# VK49_2_0.net
KiCad netlist of a schematic drawn in EAGLE
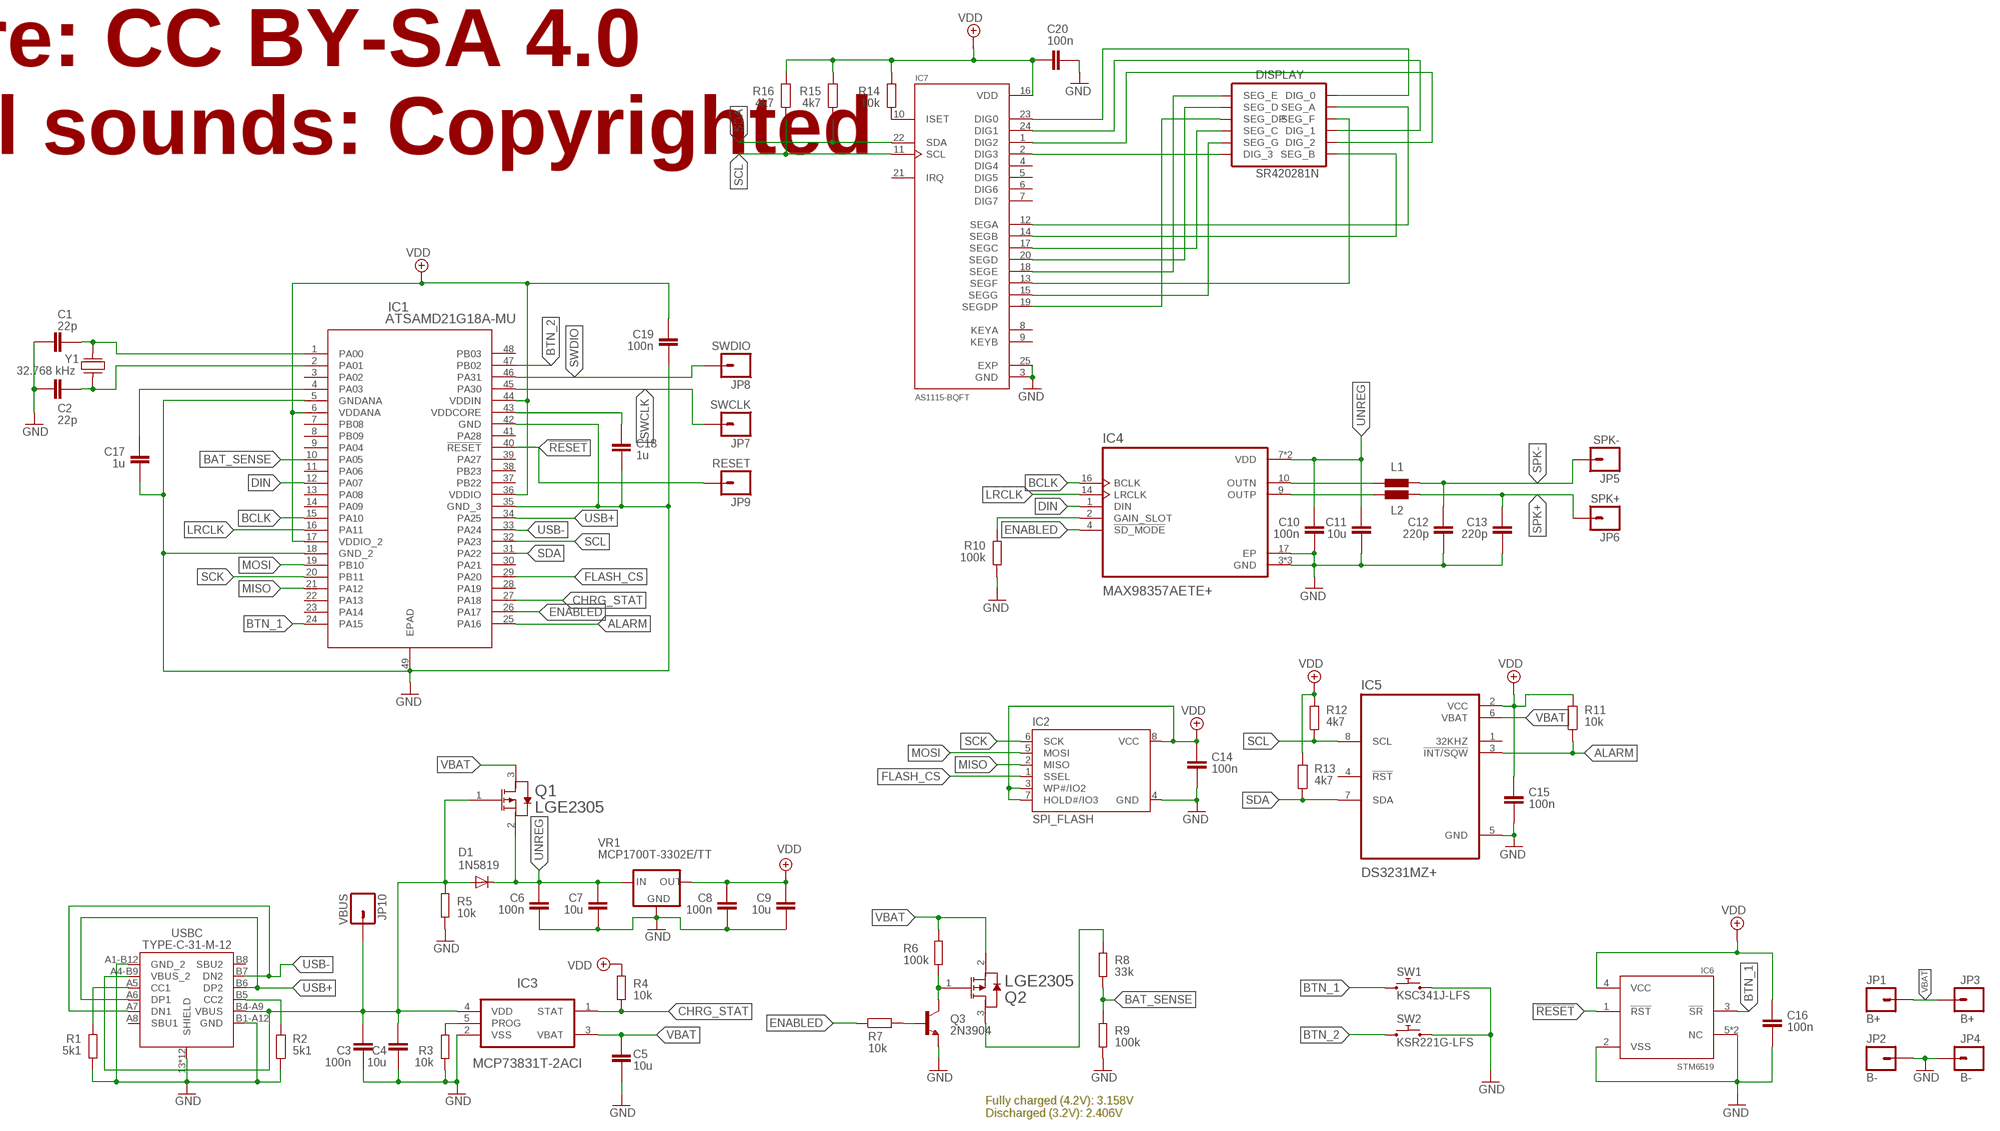
[diagram p0: schematic, sheet 1]

(export (version "E")
  (design (tool "Eeschema 10.0.6"))
  (components
    (comp (ref "C1")
      (value "22p")
      (footprint "eagle-import:CAPACITOR0603")
      (libsource (lib "eagle-import") (part "CAPACITOR0603"))
    )
    (comp (ref "C2")
      (value "22p")
      (footprint "eagle-import:CAPACITOR0603")
      (libsource (lib "eagle-import") (part "CAPACITOR0603"))
    )
    (comp (ref "C3")
      (value "100n")
      (footprint "eagle-import:CAPACITOR0603")
      (libsource (lib "eagle-import") (part "CAPACITOR0603"))
    )
    (comp (ref "C4")
      (value "10u")
      (footprint "eagle-import:CAPACITOR0805")
      (libsource (lib "eagle-import") (part "CAPACITOR0805"))
    )
    (comp (ref "C5")
      (value "10u")
      (footprint "eagle-import:CAPACITOR0805")
      (libsource (lib "eagle-import") (part "CAPACITOR0805"))
    )
    (comp (ref "C6")
      (value "100n")
      (footprint "eagle-import:CAPACITOR0603")
      (libsource (lib "eagle-import") (part "CAPACITOR0603"))
    )
    (comp (ref "C7")
      (value "10u")
      (footprint "eagle-import:CAPACITOR0805")
      (libsource (lib "eagle-import") (part "CAPACITOR0805"))
    )
    (comp (ref "C8")
      (value "100n")
      (footprint "eagle-import:CAPACITOR0603")
      (libsource (lib "eagle-import") (part "CAPACITOR0603"))
    )
    (comp (ref "C9")
      (value "10u")
      (footprint "eagle-import:CAPACITOR0805")
      (libsource (lib "eagle-import") (part "CAPACITOR0805"))
    )
    (comp (ref "C10")
      (value "100n")
      (footprint "eagle-import:CAPACITOR0603")
      (libsource (lib "eagle-import") (part "CAPACITOR0603"))
    )
    (comp (ref "C11")
      (value "10u")
      (footprint "eagle-import:CAPACITOR0805")
      (libsource (lib "eagle-import") (part "CAPACITOR0805"))
    )
    (comp (ref "C12")
      (value "220p")
      (footprint "eagle-import:CAPACITOR0603")
      (libsource (lib "eagle-import") (part "CAPACITOR0603"))
    )
    (comp (ref "C13")
      (value "220p")
      (footprint "eagle-import:CAPACITOR0603")
      (libsource (lib "eagle-import") (part "CAPACITOR0603"))
    )
    (comp (ref "C14")
      (value "100n")
      (footprint "eagle-import:CAPACITOR0603")
      (libsource (lib "eagle-import") (part "CAPACITOR0603"))
    )
    (comp (ref "C15")
      (value "100n")
      (footprint "eagle-import:CAPACITOR0603")
      (libsource (lib "eagle-import") (part "CAPACITOR0603"))
    )
    (comp (ref "C16")
      (value "100n")
      (footprint "eagle-import:CAPACITOR0603")
      (libsource (lib "eagle-import") (part "CAPACITOR0603"))
    )
    (comp (ref "C17")
      (value "1u")
      (footprint "eagle-import:CAPACITOR0603")
      (libsource (lib "eagle-import") (part "CAPACITOR0603"))
    )
    (comp (ref "C18")
      (value "1u")
      (footprint "eagle-import:CAPACITOR0603")
      (libsource (lib "eagle-import") (part "CAPACITOR0603"))
    )
    (comp (ref "C19")
      (value "100n")
      (footprint "eagle-import:CAPACITOR0603")
      (libsource (lib "eagle-import") (part "CAPACITOR0603"))
    )
    (comp (ref "C20")
      (value "100n")
      (footprint "eagle-import:CAPACITOR0603")
      (libsource (lib "eagle-import") (part "CAPACITOR0603"))
    )
    (comp (ref "D1")
      (value "1N5819")
      (footprint "eagle-import:SOD123")
      (fields (field (name "MPN") "CRS01(TE85L,Q,M) "))
      (libsource (lib "eagle-import") (part "CRS01"))
    )
    (comp (ref "DISPLAY")
      (value "SR420281N")
      (footprint "eagle-import:SEG_SR420281N_NO-SILK")
      (libsource (lib "eagle-import") (part "SEG_SR420281N_NOSILK"))
    )
    (comp (ref "IC1")
      (value "ATSAMD21G18A-MU")
      (footprint "eagle-import:QFN-48-7X7")
      (fields
        (field (name "MANUFACTURER_PART_NUMBER") "ATSAMD21G18A-MUT")
        (field (name "COPYRIGHT") "Copyright (C) 2022 Ultra Librarian. All rights reserved.")
      )
      (libsource (lib "eagle-import") (part "ATSAMD21G18A-MU"))
    )
    (comp (ref "IC2")
      (value "SPI_FLASH")
      (footprint "eagle-import:SO08-EIAJ")
      (libsource (lib "eagle-import") (part "SPI_FLASH"))
    )
    (comp (ref "IC3")
      (value "MCP73831T-2ACI")
      (footprint "eagle-import:SOT23-5")
      (fields (field (name "MPN") "MCP73831T-2ACI/OT"))
      (libsource (lib "eagle-import") (part "MCP73831T-2ACI"))
    )
    (comp (ref "IC4")
      (value "MAX98357AETE+")
      (footprint "eagle-import:QFN50P300X300X80-17N")
      (fields (field (name "MF") "Analog Devices"))
      (libsource (lib "eagle-import") (part "MAX98357AETE+"))
    )
    (comp (ref "IC5")
      (value "DS3231MZ+")
      (footprint "eagle-import:SO8")
      (fields
        (field (name "DIGI-KEY_PART_NUMBER") "DS3231MZ+-ND")
        (field (name "MF") "Maxim Integrated Products")
      )
      (libsource (lib "eagle-import") (part "DS3231MZ+"))
    )
    (comp (ref "IC6")
      (value "STM6519")
      (footprint "eagle-import:SON50P145X100X65-6N")
      (fields (field (name "MF") "STMicroelectronics") (field (name "MP") "STM6519AHARUB6F"))
      (libsource (lib "eagle-import") (part "STM6519"))
    )
    (comp (ref "IC7")
      (value "AS1115-BQFT")
      (footprint "eagle-import:QFN50P400X400X65-25N")
      (fields (field (name "DIGI-KEY_PART_NUMBER") "AS1115-BQFTTR-ND") (field (name "MF") "ams"))
      (libsource (lib "eagle-import") (part "AS1115-BQFT"))
    )
    (comp (ref "JP1")
      (value "B+")
      (footprint "eagle-import:1X01_ROUND_NOSILK")
      (libsource (lib "eagle-import") (part "M01_ROUND_NO_SILK"))
    )
    (comp (ref "JP2")
      (value "B-")
      (footprint "eagle-import:1X01_ROUND_NOSILK")
      (libsource (lib "eagle-import") (part "M01_ROUND_NO_SILK"))
    )
    (comp (ref "JP3")
      (value "B+")
      (footprint "eagle-import:1X01_ROUND_NOSILK")
      (libsource (lib "eagle-import") (part "M01_ROUND_NO_SILK"))
    )
    (comp (ref "JP4")
      (value "B-")
      (footprint "eagle-import:1X01_ROUND_NOSILK")
      (libsource (lib "eagle-import") (part "M01_ROUND_NO_SILK"))
    )
    (comp (ref "JP5")
      (value "SPK-")
      (footprint "eagle-import:1X01_ROUND_NOSILK")
      (libsource (lib "eagle-import") (part "M01_ROUND_NO_SILK"))
    )
    (comp (ref "JP6")
      (value "SPK+")
      (footprint "eagle-import:1X01_ROUND_NOSILK")
      (libsource (lib "eagle-import") (part "M01_ROUND_NO_SILK"))
    )
    (comp (ref "JP7")
      (value "SWCLK")
      (footprint "eagle-import:1X01_ROUND_NOSILK")
      (libsource (lib "eagle-import") (part "M01_ROUND_NO_SILK"))
    )
    (comp (ref "JP8")
      (value "SWDIO")
      (footprint "eagle-import:1X01_ROUND_NOSILK")
      (libsource (lib "eagle-import") (part "M01_ROUND_NO_SILK"))
    )
    (comp (ref "JP9")
      (value "RESET")
      (footprint "eagle-import:1X01_ROUND_NOSILK")
      (libsource (lib "eagle-import") (part "M01_ROUND_NO_SILK"))
    )
    (comp (ref "JP10")
      (value "VBUS")
      (footprint "eagle-import:1X01_ROUND_NOSILK")
      (libsource (lib "eagle-import") (part "M01_ROUND_NO_SILK"))
    )
    (comp (ref "L1")
      (value "MMZ1608B121CTAH0")
      (footprint "eagle-import:0603")
      (libsource (lib "eagle-import") (part "BLM15H0603"))
    )
    (comp (ref "L2")
      (value "MMZ1608B121CTAH0")
      (footprint "eagle-import:0603")
      (libsource (lib "eagle-import") (part "BLM15H0603"))
    )
    (comp (ref "Q1")
      (value "LGE2305")
      (footprint "eagle-import:SOT23")
      (libsource (lib "eagle-import") (part "LGE2305"))
    )
    (comp (ref "Q2")
      (value "LGE2305")
      (footprint "eagle-import:SOT23")
      (libsource (lib "eagle-import") (part "LGE2305"))
    )
    (comp (ref "Q3")
      (value "2N3904")
      (footprint "eagle-import:SOT23")
      (fields (field (name "MPN") "MMBT3904LT1G"))
      (libsource (lib "eagle-import") (part "2N3904"))
    )
    (comp (ref "R1")
      (value "5k1")
      (footprint "eagle-import:RESISTOR0603")
      (libsource (lib "eagle-import") (part "RESISTOR0603"))
    )
    (comp (ref "R2")
      (value "5k1")
      (footprint "eagle-import:RESISTOR0603")
      (libsource (lib "eagle-import") (part "RESISTOR0603"))
    )
    (comp (ref "R3")
      (value "10k")
      (footprint "eagle-import:RESISTOR0603")
      (libsource (lib "eagle-import") (part "RESISTOR0603"))
    )
    (comp (ref "R4")
      (value "10k")
      (footprint "eagle-import:RESISTOR0603")
      (libsource (lib "eagle-import") (part "RESISTOR0603"))
    )
    (comp (ref "R5")
      (value "10k")
      (footprint "eagle-import:RESISTOR0603")
      (libsource (lib "eagle-import") (part "RESISTOR0603"))
    )
    (comp (ref "R6")
      (value "100k")
      (footprint "eagle-import:RESISTOR0603")
      (libsource (lib "eagle-import") (part "RESISTOR0603"))
    )
    (comp (ref "R7")
      (value "10k")
      (footprint "eagle-import:RESISTOR0603")
      (libsource (lib "eagle-import") (part "RESISTOR0603"))
    )
    (comp (ref "R8")
      (value "33k")
      (footprint "eagle-import:RESISTOR0603")
      (libsource (lib "eagle-import") (part "RESISTOR0603"))
    )
    (comp (ref "R9")
      (value "100k")
      (footprint "eagle-import:RESISTOR0603")
      (libsource (lib "eagle-import") (part "RESISTOR0603"))
    )
    (comp (ref "R10")
      (value "100k")
      (footprint "eagle-import:RESISTOR0603")
      (libsource (lib "eagle-import") (part "RESISTOR0603"))
    )
    (comp (ref "R11")
      (value "10k")
      (footprint "eagle-import:RESISTOR0603")
      (libsource (lib "eagle-import") (part "RESISTOR0603"))
    )
    (comp (ref "R12")
      (value "4k7")
      (footprint "eagle-import:RESISTOR0603")
      (libsource (lib "eagle-import") (part "RESISTOR0603"))
    )
    (comp (ref "R13")
      (value "4k7")
      (footprint "eagle-import:RESISTOR0603")
      (libsource (lib "eagle-import") (part "RESISTOR0603"))
    )
    (comp (ref "R14")
      (value "10k")
      (footprint "eagle-import:RESISTOR0603")
      (libsource (lib "eagle-import") (part "RESISTOR0603"))
    )
    (comp (ref "R15")
      (value "4k7")
      (footprint "eagle-import:RESISTOR0603")
      (libsource (lib "eagle-import") (part "RESISTOR0603"))
    )
    (comp (ref "R16")
      (value "4k7")
      (footprint "eagle-import:RESISTOR0603")
      (libsource (lib "eagle-import") (part "RESISTOR0603"))
    )
    (comp (ref "SW1")
      (value "KSC341J-LFS")
      (footprint "eagle-import:KSC3XXJ")
      (libsource (lib "eagle-import") (part "KSC3XXJ"))
    )
    (comp (ref "SW2")
      (value "KSR221G-LFS")
      (footprint "eagle-import:KSR2XXG")
      (libsource (lib "eagle-import") (part "KSR2XXG"))
    )
    (comp (ref "USBC")
      (value "TYPE-C-31-M-12")
      (footprint "eagle-import:USB-C")
      (libsource (lib "eagle-import") (part "USB-C"))
    )
    (comp (ref "VR1")
      (value "MCP1700T-3302E/TT")
      (footprint "eagle-import:SOT23")
      (libsource (lib "eagle-import") (part "MCP1700T-3302E/TT"))
    )
    (comp (ref "Y1")
      (value "32.768 kHz")
      (footprint "eagle-import:3.2X1.5-2-PAD")
      (libsource (lib "eagle-import") (part "CRYSTAL_3.2X1.5"))
    )
  )
  (nets
    (net (code "1") (name "/~{RESET}") (class "Default")
      (node (ref "IC1") (pin "40") (pinfunction "~{RESET}_40") (pintype "passive"))
      (node (ref "IC6") (pin "1") (pinfunction "~{RST}_1") (pintype "output"))
      (node (ref "JP9") (pin "1") (pinfunction "1_1") (pintype "passive"))
    )
    (net (code "2") (name "ALARM") (class "Default")
      (node (ref "IC1") (pin "25") (pinfunction "PA16_25") (pintype "bidirectional"))
      (node (ref "IC5") (pin "3") (pinfunction "~{INT/SQW}_3") (pintype "output"))
      (node (ref "R11") (pin "1") (pinfunction "1_1") (pintype "passive"))
    )
    (net (code "3") (name "BAT_SENSE") (class "Default")
      (node (ref "IC1") (pin "10") (pinfunction "PA05_10") (pintype "bidirectional"))
      (node (ref "R8") (pin "2") (pinfunction "2_2") (pintype "passive"))
      (node (ref "R9") (pin "1") (pinfunction "1_1") (pintype "passive"))
    )
    (net (code "4") (name "BCLK") (class "Default")
      (node (ref "IC1") (pin "15") (pinfunction "PA10_15") (pintype "bidirectional"))
      (node (ref "IC4") (pin "16") (pinfunction "BCLK_16") (pintype "input"))
    )
    (net (code "5") (name "BTN_1") (class "Default")
      (node (ref "IC1") (pin "24") (pinfunction "PA15_24") (pintype "bidirectional"))
      (node (ref "IC6") (pin "3") (pinfunction "~{SR}_3") (pintype "input"))
      (node (ref "SW1") (pin "1") (pinfunction "1_1") (pintype "passive"))
      (node (ref "SW1") (pin "3") (pinfunction "1_3") (pintype "passive"))
    )
    (net (code "6") (name "BTN_2") (class "Default")
      (node (ref "IC1") (pin "47") (pinfunction "PB02_47") (pintype "bidirectional"))
      (node (ref "SW2") (pin "1") (pinfunction "1_1") (pintype "passive"))
    )
    (net (code "7") (name "CHRG_STAT") (class "Default")
      (node (ref "IC1") (pin "27") (pinfunction "PA18_27") (pintype "bidirectional"))
      (node (ref "IC3") (pin "1") (pinfunction "STAT_1") (pintype "output"))
      (node (ref "R4") (pin "1") (pinfunction "1_1") (pintype "passive"))
    )
    (net (code "8") (name "DIN") (class "Default")
      (node (ref "IC1") (pin "12") (pinfunction "PA07_12") (pintype "bidirectional"))
      (node (ref "IC4") (pin "1") (pinfunction "DIN_1") (pintype "input"))
    )
    (net (code "9") (name "ENABLED") (class "Default")
      (node (ref "IC1") (pin "26") (pinfunction "PA17_26") (pintype "bidirectional"))
      (node (ref "IC4") (pin "4") (pinfunction "~{SD_MODE}_4") (pintype "input"))
      (node (ref "R7") (pin "1") (pinfunction "1_1") (pintype "passive"))
    )
    (net (code "10") (name "FLASH_CS") (class "Default")
      (node (ref "IC1") (pin "29") (pinfunction "PA20_29") (pintype "bidirectional"))
      (node (ref "IC2") (pin "1") (pinfunction "SSEL_1") (pintype "bidirectional"))
    )
    (net (code "11") (name "GND") (class "Default")
      (node (ref "C1") (pin "1") (pinfunction "1_1") (pintype "passive"))
      (node (ref "C10") (pin "1") (pinfunction "1_1") (pintype "passive"))
      (node (ref "C11") (pin "2") (pinfunction "2_2") (pintype "passive"))
      (node (ref "C12") (pin "1") (pinfunction "1_1") (pintype "passive"))
      (node (ref "C13") (pin "1") (pinfunction "1_1") (pintype "passive"))
      (node (ref "C14") (pin "1") (pinfunction "1_1") (pintype "passive"))
      (node (ref "C15") (pin "1") (pinfunction "1_1") (pintype "passive"))
      (node (ref "C16") (pin "1") (pinfunction "1_1") (pintype "passive"))
      (node (ref "C17") (pin "1") (pinfunction "1_1") (pintype "passive"))
      (node (ref "C18") (pin "1") (pinfunction "1_1") (pintype "passive"))
      (node (ref "C19") (pin "1") (pinfunction "1_1") (pintype "passive"))
      (node (ref "C2") (pin "1") (pinfunction "1_1") (pintype "passive"))
      (node (ref "C20") (pin "1") (pinfunction "1_1") (pintype "passive"))
      (node (ref "C3") (pin "1") (pinfunction "1_1") (pintype "passive"))
      (node (ref "C4") (pin "2") (pinfunction "2_2") (pintype "passive"))
      (node (ref "C5") (pin "2") (pinfunction "2_2") (pintype "passive"))
      (node (ref "C6") (pin "1") (pinfunction "1_1") (pintype "passive"))
      (node (ref "C7") (pin "2") (pinfunction "2_2") (pintype "passive"))
      (node (ref "C8") (pin "1") (pinfunction "1_1") (pintype "passive"))
      (node (ref "C9") (pin "2") (pinfunction "2_2") (pintype "passive"))
      (node (ref "IC1") (pin "18") (pinfunction "GND_2_18") (pintype "passive"))
      (node (ref "IC1") (pin "35") (pinfunction "GND_3_35") (pintype "passive"))
      (node (ref "IC1") (pin "42") (pinfunction "GND_42") (pintype "passive"))
      (node (ref "IC1") (pin "49") (pinfunction "EPAD_49") (pintype "passive"))
      (node (ref "IC1") (pin "5") (pinfunction "GNDANA_5") (pintype "passive"))
      (node (ref "IC2") (pin "4") (pinfunction "GND_4") (pintype "power_in"))
      (node (ref "IC3") (pin "2") (pinfunction "VSS_2") (pintype "power_in"))
      (node (ref "IC4") (pin "11") (pinfunction "GND_11") (pintype "power_in"))
      (node (ref "IC4") (pin "15") (pinfunction "GND_15") (pintype "power_in"))
      (node (ref "IC4") (pin "17") (pinfunction "EP_17") (pintype "power_in"))
      (node (ref "IC4") (pin "3") (pinfunction "GND_3") (pintype "power_in"))
      (node (ref "IC5") (pin "5") (pinfunction "GND_5") (pintype "power_in"))
      (node (ref "IC6") (pin "2") (pinfunction "VSS_2") (pintype "power_in"))
      (node (ref "IC6") (pin "5") (pinfunction "NC_5") (pintype "passive"))
      (node (ref "IC6") (pin "6") (pinfunction "NC_6") (pintype "passive"))
      (node (ref "IC7") (pin "25") (pinfunction "EXP_25") (pintype "passive"))
      (node (ref "IC7") (pin "3") (pinfunction "GND_3") (pintype "power_in"))
      (node (ref "JP2") (pin "1") (pinfunction "1_1") (pintype "passive"))
      (node (ref "JP4") (pin "1") (pinfunction "1_1") (pintype "passive"))
      (node (ref "Q3") (pin "2") (pinfunction "E_2") (pintype "passive"))
      (node (ref "R1") (pin "1") (pinfunction "1_1") (pintype "passive"))
      (node (ref "R10") (pin "1") (pinfunction "1_1") (pintype "passive"))
      (node (ref "R2") (pin "1") (pinfunction "1_1") (pintype "passive"))
      (node (ref "R3") (pin "2") (pinfunction "2_2") (pintype "passive"))
      (node (ref "R5") (pin "1") (pinfunction "1_1") (pintype "passive"))
      (node (ref "R9") (pin "2") (pinfunction "2_2") (pintype "passive"))
      (node (ref "SW1") (pin "2") (pinfunction "2_2") (pintype "passive"))
      (node (ref "SW1") (pin "4") (pinfunction "2_4") (pintype "passive"))
      (node (ref "SW2") (pin "2") (pinfunction "2_2") (pintype "passive"))
      (node (ref "USBC") (pin "13") (pinfunction "SHIELD_13") (pintype "bidirectional"))
      (node (ref "USBC") (pin "14") (pinfunction "SHIELD_14") (pintype "bidirectional"))
      (node (ref "USBC") (pin "15") (pinfunction "SHIELD_15") (pintype "bidirectional"))
      (node (ref "USBC") (pin "16") (pinfunction "SHIELD_16") (pintype "bidirectional"))
      (node (ref "USBC") (pin "A1-B12") (pinfunction "GND_2_A1-B12") (pintype "passive"))
      (node (ref "USBC") (pin "B1-A12") (pinfunction "GND_B1-A12") (pintype "passive"))
      (node (ref "USBC") (pin "S_1_H1") (pinfunction "SHIELD_S_1_H1") (pintype "bidirectional"))
      (node (ref "USBC") (pin "S_1_H2") (pinfunction "SHIELD_S_1_H2") (pintype "bidirectional"))
      (node (ref "USBC") (pin "S_2_H1") (pinfunction "SHIELD_S_2_H1") (pintype "bidirectional"))
      (node (ref "USBC") (pin "S_2_H2") (pinfunction "SHIELD_S_2_H2") (pintype "bidirectional"))
      (node (ref "USBC") (pin "S_3_H1") (pinfunction "SHIELD_S_3_H1") (pintype "bidirectional"))
      (node (ref "USBC") (pin "S_3_H2") (pinfunction "SHIELD_S_3_H2") (pintype "bidirectional"))
      (node (ref "USBC") (pin "S_4_H1") (pinfunction "SHIELD_S_4_H1") (pintype "bidirectional"))
      (node (ref "USBC") (pin "S_4_H2") (pinfunction "SHIELD_S_4_H2") (pintype "bidirectional"))
      (node (ref "VR1") (pin "GND") (pinfunction "GND_GND") (pintype "input"))
    )
    (net (code "12") (name "LRCLK") (class "Default")
      (node (ref "IC1") (pin "16") (pinfunction "PA11_16") (pintype "bidirectional"))
      (node (ref "IC4") (pin "14") (pinfunction "LRCLK_14") (pintype "input"))
    )
    (net (code "13") (name "MISO") (class "Default")
      (node (ref "IC1") (pin "21") (pinfunction "PA12_21") (pintype "bidirectional"))
      (node (ref "IC2") (pin "2") (pinfunction "MISO_2") (pintype "bidirectional"))
    )
    (net (code "14") (name "MOSI") (class "Default")
      (node (ref "IC1") (pin "19") (pinfunction "PB10_19") (pintype "bidirectional"))
      (node (ref "IC2") (pin "5") (pinfunction "MOSI_5") (pintype "bidirectional"))
    )
    (net (code "15") (name "Net-(DISPLAY-DIG_0)") (class "Default")
      (node (ref "DISPLAY") (pin "12") (pinfunction "DIG_0_12") (pintype "bidirectional"))
      (node (ref "IC7") (pin "23") (pinfunction "DIG0_23") (pintype "output"))
    )
    (net (code "16") (name "Net-(DISPLAY-DIG_1)") (class "Default")
      (node (ref "DISPLAY") (pin "9") (pinfunction "DIG_1_9") (pintype "bidirectional"))
      (node (ref "IC7") (pin "24") (pinfunction "DIG1_24") (pintype "output"))
    )
    (net (code "17") (name "Net-(DISPLAY-DIG_2)") (class "Default")
      (node (ref "DISPLAY") (pin "8") (pinfunction "DIG_2_8") (pintype "bidirectional"))
      (node (ref "IC7") (pin "1") (pinfunction "DIG2_1") (pintype "output"))
    )
    (net (code "18") (name "Net-(DISPLAY-DIG_3)") (class "Default")
      (node (ref "DISPLAY") (pin "6") (pinfunction "DIG_3_6") (pintype "bidirectional"))
      (node (ref "IC7") (pin "2") (pinfunction "DIG3_2") (pintype "output"))
    )
    (net (code "19") (name "Net-(DISPLAY-SEG_A)") (class "Default")
      (node (ref "DISPLAY") (pin "11") (pinfunction "SEG_A_11") (pintype "bidirectional"))
      (node (ref "IC7") (pin "12") (pinfunction "SEGA_12") (pintype "output"))
    )
    (net (code "20") (name "Net-(DISPLAY-SEG_B)") (class "Default")
      (node (ref "DISPLAY") (pin "7") (pinfunction "SEG_B_7") (pintype "bidirectional"))
      (node (ref "IC7") (pin "14") (pinfunction "SEGB_14") (pintype "output"))
    )
    (net (code "21") (name "Net-(DISPLAY-SEG_C)") (class "Default")
      (node (ref "DISPLAY") (pin "4") (pinfunction "SEG_C_4") (pintype "bidirectional"))
      (node (ref "IC7") (pin "17") (pinfunction "SEGC_17") (pintype "output"))
    )
    (net (code "22") (name "Net-(DISPLAY-SEG_D)") (class "Default")
      (node (ref "DISPLAY") (pin "2") (pinfunction "SEG_D_2") (pintype "bidirectional"))
      (node (ref "IC7") (pin "20") (pinfunction "SEGD_20") (pintype "output"))
    )
    (net (code "23") (name "Net-(DISPLAY-SEG_DP)") (class "Default")
      (node (ref "DISPLAY") (pin "3") (pinfunction "SEG_DP_3") (pintype "bidirectional"))
      (node (ref "IC7") (pin "19") (pinfunction "SEGDP_19") (pintype "output"))
    )
    (net (code "24") (name "Net-(DISPLAY-SEG_E)") (class "Default")
      (node (ref "DISPLAY") (pin "1") (pinfunction "SEG_E_1") (pintype "bidirectional"))
      (node (ref "IC7") (pin "18") (pinfunction "SEGE_18") (pintype "output"))
    )
    (net (code "25") (name "Net-(DISPLAY-SEG_F)") (class "Default")
      (node (ref "DISPLAY") (pin "10") (pinfunction "SEG_F_10") (pintype "bidirectional"))
      (node (ref "IC7") (pin "13") (pinfunction "SEGF_13") (pintype "output"))
    )
    (net (code "26") (name "Net-(DISPLAY-SEG_G)") (class "Default")
      (node (ref "DISPLAY") (pin "5") (pinfunction "SEG_G_5") (pintype "bidirectional"))
      (node (ref "IC7") (pin "15") (pinfunction "SEGG_15") (pintype "output"))
    )
    (net (code "27") (name "Net-(IC1-PA00)") (class "Default")
      (node (ref "C1") (pin "2") (pinfunction "2_2") (pintype "passive"))
      (node (ref "IC1") (pin "1") (pinfunction "PA00_1") (pintype "bidirectional"))
      (node (ref "Y1") (pin "1") (pinfunction "P$1_1") (pintype "bidirectional"))
    )
    (net (code "28") (name "Net-(IC1-PA01)") (class "Default")
      (node (ref "C2") (pin "2") (pinfunction "2_2") (pintype "passive"))
      (node (ref "IC1") (pin "2") (pinfunction "PA01_2") (pintype "bidirectional"))
      (node (ref "Y1") (pin "2") (pinfunction "P$2_2") (pintype "bidirectional"))
    )
    (net (code "29") (name "Net-(IC1-PA03)") (class "Default")
      (node (ref "C17") (pin "2") (pinfunction "2_2") (pintype "passive"))
      (node (ref "IC1") (pin "4") (pinfunction "PA03_4") (pintype "bidirectional"))
    )
    (net (code "30") (name "Net-(IC1-VDDCORE)") (class "Default")
      (node (ref "C18") (pin "2") (pinfunction "2_2") (pintype "passive"))
      (node (ref "IC1") (pin "43") (pinfunction "VDDCORE_43") (pintype "power_in"))
    )
    (net (code "31") (name "Net-(IC3-PROG)") (class "Default")
      (node (ref "IC3") (pin "5") (pinfunction "PROG_5") (pintype "input"))
      (node (ref "R3") (pin "1") (pinfunction "1_1") (pintype "passive"))
    )
    (net (code "32") (name "Net-(IC3-VDD)") (class "Default")
      (node (ref "C3") (pin "2") (pinfunction "2_2") (pintype "passive"))
      (node (ref "C4") (pin "1") (pinfunction "1_1") (pintype "passive"))
      (node (ref "D1") (pin "A") (pinfunction "A_A") (pintype "passive"))
      (node (ref "IC3") (pin "4") (pinfunction "VDD_4") (pintype "power_in"))
      (node (ref "JP10") (pin "1") (pinfunction "1_1") (pintype "passive"))
      (node (ref "Q1") (pin "1") (pinfunction "GATE_1") (pintype "passive"))
      (node (ref "R5") (pin "2") (pinfunction "2_2") (pintype "passive"))
      (node (ref "USBC") (pin "A4-B9") (pinfunction "VBUS_2_A4-B9") (pintype "power_in"))
      (node (ref "USBC") (pin "B4-A9") (pinfunction "VBUS_B4-A9") (pintype "power_in"))
    )
    (net (code "33") (name "Net-(IC4-GAIN_SLOT)") (class "Default")
      (node (ref "IC4") (pin "2") (pinfunction "GAIN_SLOT_2") (pintype "input"))
      (node (ref "R10") (pin "2") (pinfunction "2_2") (pintype "passive"))
    )
    (net (code "34") (name "Net-(IC4-OUTN)") (class "Default")
      (node (ref "IC4") (pin "10") (pinfunction "OUTN_10") (pintype "output"))
      (node (ref "L1") (pin "1") (pinfunction "1_1") (pintype "passive"))
    )
    (net (code "35") (name "Net-(IC4-OUTP)") (class "Default")
      (node (ref "IC4") (pin "9") (pinfunction "OUTP_9") (pintype "output"))
      (node (ref "L2") (pin "1") (pinfunction "1_1") (pintype "passive"))
    )
    (net (code "36") (name "Net-(IC7-ISET)") (class "Default")
      (node (ref "IC7") (pin "10") (pinfunction "ISET_10") (pintype "passive"))
      (node (ref "R14") (pin "1") (pinfunction "1_1") (pintype "passive"))
    )
    (net (code "37") (name "Net-(Q2-DRAIN)") (class "Default")
      (node (ref "Q2") (pin "3") (pinfunction "DRAIN_3") (pintype "passive"))
      (node (ref "R8") (pin "1") (pinfunction "1_1") (pintype "passive"))
    )
    (net (code "38") (name "Net-(Q2-GATE)") (class "Default")
      (node (ref "Q2") (pin "1") (pinfunction "GATE_1") (pintype "passive"))
      (node (ref "Q3") (pin "3") (pinfunction "C_3") (pintype "passive"))
      (node (ref "R6") (pin "2") (pinfunction "2_2") (pintype "passive"))
    )
    (net (code "39") (name "Net-(Q3-B)") (class "Default")
      (node (ref "Q3") (pin "1") (pinfunction "B_1") (pintype "passive"))
      (node (ref "R7") (pin "2") (pinfunction "2_2") (pintype "passive"))
    )
    (net (code "40") (name "Net-(USBC-CC1)") (class "Default")
      (node (ref "R1") (pin "2") (pinfunction "2_2") (pintype "passive"))
      (node (ref "USBC") (pin "A5") (pinfunction "CC1_A5") (pintype "bidirectional"))
    )
    (net (code "41") (name "Net-(USBC-CC2)") (class "Default")
      (node (ref "R2") (pin "2") (pinfunction "2_2") (pintype "passive"))
      (node (ref "USBC") (pin "B5") (pinfunction "CC2_B5") (pintype "bidirectional"))
    )
    (net (code "42") (name "SCK") (class "Default")
      (node (ref "IC1") (pin "20") (pinfunction "PB11_20") (pintype "bidirectional"))
      (node (ref "IC2") (pin "6") (pinfunction "SCK_6") (pintype "bidirectional"))
    )
    (net (code "43") (name "SCL") (class "Default")
      (node (ref "IC1") (pin "32") (pinfunction "PA23_32") (pintype "bidirectional"))
      (node (ref "IC5") (pin "8") (pinfunction "SCL_8") (pintype "input"))
      (node (ref "IC7") (pin "11") (pinfunction "SCL_11") (pintype "input"))
      (node (ref "R12") (pin "1") (pinfunction "1_1") (pintype "passive"))
      (node (ref "R16") (pin "1") (pinfunction "1_1") (pintype "passive"))
    )
    (net (code "44") (name "SDA") (class "Default")
      (node (ref "IC1") (pin "31") (pinfunction "PA22_31") (pintype "bidirectional"))
      (node (ref "IC5") (pin "7") (pinfunction "SDA_7") (pintype "bidirectional"))
      (node (ref "IC7") (pin "22") (pinfunction "SDA_22") (pintype "bidirectional"))
      (node (ref "R13") (pin "1") (pinfunction "1_1") (pintype "passive"))
      (node (ref "R15") (pin "1") (pinfunction "1_1") (pintype "passive"))
    )
    (net (code "45") (name "SPK+") (class "Default")
      (node (ref "C13") (pin "2") (pinfunction "2_2") (pintype "passive"))
      (node (ref "JP6") (pin "1") (pinfunction "1_1") (pintype "passive"))
      (node (ref "L2") (pin "2") (pinfunction "2_2") (pintype "passive"))
    )
    (net (code "46") (name "SPK-") (class "Default")
      (node (ref "C12") (pin "2") (pinfunction "2_2") (pintype "passive"))
      (node (ref "JP5") (pin "1") (pinfunction "1_1") (pintype "passive"))
      (node (ref "L1") (pin "2") (pinfunction "2_2") (pintype "passive"))
    )
    (net (code "47") (name "SWCLK") (class "Default")
      (node (ref "IC1") (pin "45") (pinfunction "PA30_45") (pintype "bidirectional"))
      (node (ref "JP7") (pin "1") (pinfunction "1_1") (pintype "passive"))
    )
    (net (code "48") (name "SWDIO") (class "Default")
      (node (ref "IC1") (pin "46") (pinfunction "PA31_46") (pintype "bidirectional"))
      (node (ref "JP8") (pin "1") (pinfunction "1_1") (pintype "passive"))
    )
    (net (code "49") (name "UNREG") (class "Default")
      (node (ref "C10") (pin "2") (pinfunction "2_2") (pintype "passive"))
      (node (ref "C11") (pin "1") (pinfunction "1_1") (pintype "passive"))
      (node (ref "C6") (pin "2") (pinfunction "2_2") (pintype "passive"))
      (node (ref "C7") (pin "1") (pinfunction "1_1") (pintype "passive"))
      (node (ref "D1") (pin "C") (pinfunction "C_C") (pintype "passive"))
      (node (ref "IC4") (pin "7") (pinfunction "VDD_7") (pintype "power_in"))
      (node (ref "IC4") (pin "8") (pinfunction "VDD_8") (pintype "power_in"))
      (node (ref "Q1") (pin "2") (pinfunction "SOURCE_2") (pintype "passive"))
      (node (ref "VR1") (pin "VIN") (pinfunction "IN_VIN") (pintype "input"))
    )
    (net (code "50") (name "USB+") (class "Default")
      (node (ref "IC1") (pin "34") (pinfunction "PA25_34") (pintype "bidirectional"))
      (node (ref "USBC") (pin "A6") (pinfunction "DP1_A6") (pintype "bidirectional"))
      (node (ref "USBC") (pin "B6") (pinfunction "DP2_B6") (pintype "bidirectional"))
    )
    (net (code "51") (name "USB-") (class "Default")
      (node (ref "IC1") (pin "33") (pinfunction "PA24_33") (pintype "bidirectional"))
      (node (ref "USBC") (pin "A7") (pinfunction "DN1_A7") (pintype "bidirectional"))
      (node (ref "USBC") (pin "B7") (pinfunction "DN2_B7") (pintype "bidirectional"))
    )
    (net (code "52") (name "VBAT") (class "Default")
      (node (ref "C5") (pin "1") (pinfunction "1_1") (pintype "passive"))
      (node (ref "IC3") (pin "3") (pinfunction "VBAT_3") (pintype "output"))
      (node (ref "IC5") (pin "6") (pinfunction "VBAT_6") (pintype "power_in"))
      (node (ref "JP1") (pin "1") (pinfunction "1_1") (pintype "passive"))
      (node (ref "JP3") (pin "1") (pinfunction "1_1") (pintype "passive"))
      (node (ref "Q1") (pin "3") (pinfunction "DRAIN_3") (pintype "passive"))
      (node (ref "Q2") (pin "2") (pinfunction "SOURCE_2") (pintype "passive"))
      (node (ref "R6") (pin "1") (pinfunction "1_1") (pintype "passive"))
    )
    (net (code "53") (name "VDD") (class "Default")
      (node (ref "C14") (pin "2") (pinfunction "2_2") (pintype "passive"))
      (node (ref "C15") (pin "2") (pinfunction "2_2") (pintype "passive"))
      (node (ref "C16") (pin "2") (pinfunction "2_2") (pintype "passive"))
      (node (ref "C19") (pin "2") (pinfunction "2_2") (pintype "passive"))
      (node (ref "C20") (pin "2") (pinfunction "2_2") (pintype "passive"))
      (node (ref "C8") (pin "2") (pinfunction "2_2") (pintype "passive"))
      (node (ref "C9") (pin "1") (pinfunction "1_1") (pintype "passive"))
      (node (ref "IC1") (pin "17") (pinfunction "VDDIO_2_17") (pintype "power_in"))
      (node (ref "IC1") (pin "36") (pinfunction "VDDIO_36") (pintype "power_in"))
      (node (ref "IC1") (pin "44") (pinfunction "VDDIN_44") (pintype "power_in"))
      (node (ref "IC1") (pin "6") (pinfunction "VDDANA_6") (pintype "power_in"))
      (node (ref "IC2") (pin "3") (pinfunction "WP#/IO2_3") (pintype "bidirectional"))
      (node (ref "IC2") (pin "7") (pinfunction "HOLD#/IO3_7") (pintype "bidirectional"))
      (node (ref "IC2") (pin "8") (pinfunction "VCC_8") (pintype "power_in"))
      (node (ref "IC5") (pin "2") (pinfunction "VCC_2") (pintype "power_in"))
      (node (ref "IC6") (pin "4") (pinfunction "VCC_4") (pintype "power_in"))
      (node (ref "IC7") (pin "16") (pinfunction "VDD_16") (pintype "power_in"))
      (node (ref "R11") (pin "2") (pinfunction "2_2") (pintype "passive"))
      (node (ref "R12") (pin "2") (pinfunction "2_2") (pintype "passive"))
      (node (ref "R13") (pin "2") (pinfunction "2_2") (pintype "passive"))
      (node (ref "R14") (pin "2") (pinfunction "2_2") (pintype "passive"))
      (node (ref "R15") (pin "2") (pinfunction "2_2") (pintype "passive"))
      (node (ref "R16") (pin "2") (pinfunction "2_2") (pintype "passive"))
      (node (ref "R4") (pin "2") (pinfunction "2_2") (pintype "passive"))
      (node (ref "VR1") (pin "VOUT") (pinfunction "OUT_VOUT") (pintype "output"))
    )
    (net (code "54") (name "unconnected-(IC1-PA02-Pad3)") (class "Default")
      (node (ref "IC1") (pin "3") (pinfunction "PA02_3") (pintype "bidirectional"))
    )
    (net (code "55") (name "unconnected-(IC1-PA04-Pad9)") (class "Default")
      (node (ref "IC1") (pin "9") (pinfunction "PA04_9") (pintype "bidirectional"))
    )
    (net (code "56") (name "unconnected-(IC1-PA06-Pad11)") (class "Default")
      (node (ref "IC1") (pin "11") (pinfunction "PA06_11") (pintype "bidirectional"))
    )
    (net (code "57") (name "unconnected-(IC1-PA08-Pad13)") (class "Default")
      (node (ref "IC1") (pin "13") (pinfunction "PA08_13") (pintype "bidirectional"))
    )
    (net (code "58") (name "unconnected-(IC1-PA09-Pad14)") (class "Default")
      (node (ref "IC1") (pin "14") (pinfunction "PA09_14") (pintype "bidirectional"))
    )
    (net (code "59") (name "unconnected-(IC1-PA13-Pad22)") (class "Default")
      (node (ref "IC1") (pin "22") (pinfunction "PA13_22") (pintype "bidirectional"))
    )
    (net (code "60") (name "unconnected-(IC1-PA14-Pad23)") (class "Default")
      (node (ref "IC1") (pin "23") (pinfunction "PA14_23") (pintype "bidirectional"))
    )
    (net (code "61") (name "unconnected-(IC1-PA19-Pad28)") (class "Default")
      (node (ref "IC1") (pin "28") (pinfunction "PA19_28") (pintype "bidirectional"))
    )
    (net (code "62") (name "unconnected-(IC1-PA21-Pad30)") (class "Default")
      (node (ref "IC1") (pin "30") (pinfunction "PA21_30") (pintype "bidirectional"))
    )
    (net (code "63") (name "unconnected-(IC1-PA27-Pad39)") (class "Default")
      (node (ref "IC1") (pin "39") (pinfunction "PA27_39") (pintype "bidirectional"))
    )
    (net (code "64") (name "unconnected-(IC1-PA28-Pad41)") (class "Default")
      (node (ref "IC1") (pin "41") (pinfunction "PA28_41") (pintype "bidirectional"))
    )
    (net (code "65") (name "unconnected-(IC1-PB03-Pad48)") (class "Default")
      (node (ref "IC1") (pin "48") (pinfunction "PB03_48") (pintype "bidirectional"))
    )
    (net (code "66") (name "unconnected-(IC1-PB08-Pad7)") (class "Default")
      (node (ref "IC1") (pin "7") (pinfunction "PB08_7") (pintype "bidirectional"))
    )
    (net (code "67") (name "unconnected-(IC1-PB09-Pad8)") (class "Default")
      (node (ref "IC1") (pin "8") (pinfunction "PB09_8") (pintype "bidirectional"))
    )
    (net (code "68") (name "unconnected-(IC1-PB22-Pad37)") (class "Default")
      (node (ref "IC1") (pin "37") (pinfunction "PB22_37") (pintype "bidirectional"))
    )
    (net (code "69") (name "unconnected-(IC1-PB23-Pad38)") (class "Default")
      (node (ref "IC1") (pin "38") (pinfunction "PB23_38") (pintype "bidirectional"))
    )
    (net (code "70") (name "unconnected-(IC5-32KHZ-Pad1)") (class "Default")
      (node (ref "IC5") (pin "1") (pinfunction "32KHZ_1") (pintype "output"))
    )
    (net (code "71") (name "unconnected-(IC5-~{RST}-Pad4)") (class "Default")
      (node (ref "IC5") (pin "4") (pinfunction "~{RST}_4") (pintype "bidirectional"))
    )
    (net (code "72") (name "unconnected-(IC7-DIG4-Pad4)") (class "Default")
      (node (ref "IC7") (pin "4") (pinfunction "DIG4_4") (pintype "output"))
    )
    (net (code "73") (name "unconnected-(IC7-DIG5-Pad5)") (class "Default")
      (node (ref "IC7") (pin "5") (pinfunction "DIG5_5") (pintype "output"))
    )
    (net (code "74") (name "unconnected-(IC7-DIG6-Pad6)") (class "Default")
      (node (ref "IC7") (pin "6") (pinfunction "DIG6_6") (pintype "output"))
    )
    (net (code "75") (name "unconnected-(IC7-DIG7-Pad7)") (class "Default")
      (node (ref "IC7") (pin "7") (pinfunction "DIG7_7") (pintype "output"))
    )
    (net (code "76") (name "unconnected-(IC7-IRQ-Pad21)") (class "Default")
      (node (ref "IC7") (pin "21") (pinfunction "IRQ_21") (pintype "output"))
    )
    (net (code "77") (name "unconnected-(IC7-KEYA-Pad8)") (class "Default")
      (node (ref "IC7") (pin "8") (pinfunction "KEYA_8") (pintype "output"))
    )
    (net (code "78") (name "unconnected-(IC7-KEYB-Pad9)") (class "Default")
      (node (ref "IC7") (pin "9") (pinfunction "KEYB_9") (pintype "output"))
    )
    (net (code "79") (name "unconnected-(USBC-SBU1-PadA8)") (class "Default")
      (node (ref "USBC") (pin "A8") (pinfunction "SBU1_A8") (pintype "bidirectional"))
    )
    (net (code "80") (name "unconnected-(USBC-SBU2-PadB8)") (class "Default")
      (node (ref "USBC") (pin "B8") (pinfunction "SBU2_B8") (pintype "bidirectional"))
    )
  )
)
